# Connections.net
KiCad netlist of a schematic drawn in EAGLE
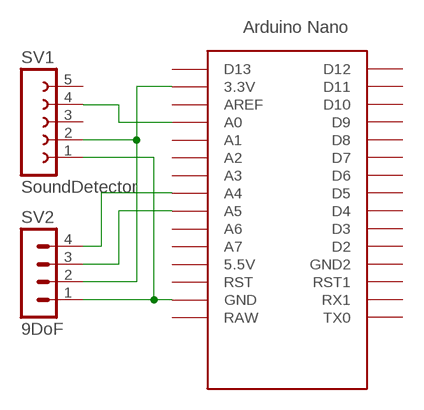
[diagram p0: schematic, sheet 1]

(export (version "E")
  (design (tool "Eeschema 10.0.6"))
  (components
    (comp (ref "SV1")
      (value "SoundDetector")
      (footprint "eagle-import:FE05-1")
      (libsource (lib "eagle-import") (part "FE05-1"))
    )
    (comp (ref "SV2")
      (value "9DoF")
      (footprint "eagle-import:MA04-1")
      (libsource (lib "eagle-import") (part "MA04-1"))
    )
    (comp (ref "U$1")
      (value "NANO")
      (footprint "eagle-import:NANO")
      (libsource (lib "eagle-import") (part "NANO"))
    )
  )
  (nets
    (net (code "1") (name "Net-(SV1-Pad1)") (class "Default")
      (node (ref "SV1") (pin "1") (pinfunction "1_1") (pintype "passive"))
      (node (ref "SV2") (pin "1") (pinfunction "1_1") (pintype "passive"))
      (node (ref "U$1") (pin "GND") (pinfunction "GND_GND") (pintype "bidirectional"))
    )
    (net (code "2") (name "Net-(SV1-Pad2)") (class "Default")
      (node (ref "SV1") (pin "2") (pinfunction "2_2") (pintype "passive"))
      (node (ref "SV2") (pin "2") (pinfunction "2_2") (pintype "passive"))
      (node (ref "U$1") (pin "3.3V") (pinfunction "3.3V_3.3V") (pintype "bidirectional"))
    )
    (net (code "3") (name "Net-(SV1-Pad4)") (class "Default")
      (node (ref "SV1") (pin "4") (pinfunction "4_4") (pintype "passive"))
      (node (ref "U$1") (pin "A0") (pinfunction "A0_A0") (pintype "bidirectional"))
    )
    (net (code "4") (name "Net-(SV2-Pad3)") (class "Default")
      (node (ref "SV2") (pin "3") (pinfunction "3_3") (pintype "passive"))
      (node (ref "U$1") (pin "A5") (pinfunction "A5_A5") (pintype "bidirectional"))
    )
    (net (code "5") (name "Net-(SV2-Pad4)") (class "Default")
      (node (ref "SV2") (pin "4") (pinfunction "4_4") (pintype "passive"))
      (node (ref "U$1") (pin "A4") (pinfunction "A4_A4") (pintype "bidirectional"))
    )
    (net (code "6") (name "unconnected-(SV1-Pad3)") (class "Default")
      (node (ref "SV1") (pin "3") (pinfunction "3_3") (pintype "passive"))
    )
    (net (code "7") (name "unconnected-(SV1-Pad5)") (class "Default")
      (node (ref "SV1") (pin "5") (pinfunction "5_5") (pintype "passive"))
    )
    (net (code "8") (name "unconnected-(U$1-5.5V-Pad5V)") (class "Default")
      (node (ref "U$1") (pin "5V") (pinfunction "5.5V_5V") (pintype "bidirectional"))
    )
    (net (code "9") (name "unconnected-(U$1-GND2-PadGND1)") (class "Default")
      (node (ref "U$1") (pin "GND1") (pinfunction "GND2_GND1") (pintype "bidirectional"))
    )
    (net (code "10") (name "unconnected-(U$1-PadA1)") (class "Default")
      (node (ref "U$1") (pin "A1") (pinfunction "A1_A1") (pintype "bidirectional"))
    )
    (net (code "11") (name "unconnected-(U$1-PadA2)") (class "Default")
      (node (ref "U$1") (pin "A2") (pinfunction "A2_A2") (pintype "bidirectional"))
    )
    (net (code "12") (name "unconnected-(U$1-PadA3)") (class "Default")
      (node (ref "U$1") (pin "A3") (pinfunction "A3_A3") (pintype "bidirectional"))
    )
    (net (code "13") (name "unconnected-(U$1-PadA6)") (class "Default")
      (node (ref "U$1") (pin "A6") (pinfunction "A6_A6") (pintype "bidirectional"))
    )
    (net (code "14") (name "unconnected-(U$1-PadA7)") (class "Default")
      (node (ref "U$1") (pin "A7") (pinfunction "A7_A7") (pintype "bidirectional"))
    )
    (net (code "15") (name "unconnected-(U$1-PadAREF)") (class "Default")
      (node (ref "U$1") (pin "AREF") (pinfunction "AREF_AREF") (pintype "bidirectional"))
    )
    (net (code "16") (name "unconnected-(U$1-PadD2)") (class "Default")
      (node (ref "U$1") (pin "D2") (pinfunction "D2_D2") (pintype "bidirectional"))
    )
    (net (code "17") (name "unconnected-(U$1-PadD3)") (class "Default")
      (node (ref "U$1") (pin "D3") (pinfunction "D3_D3") (pintype "bidirectional"))
    )
    (net (code "18") (name "unconnected-(U$1-PadD4)") (class "Default")
      (node (ref "U$1") (pin "D4") (pinfunction "D4_D4") (pintype "bidirectional"))
    )
    (net (code "19") (name "unconnected-(U$1-PadD5)") (class "Default")
      (node (ref "U$1") (pin "D5") (pinfunction "D5_D5") (pintype "bidirectional"))
    )
    (net (code "20") (name "unconnected-(U$1-PadD6)") (class "Default")
      (node (ref "U$1") (pin "D6") (pinfunction "D6_D6") (pintype "bidirectional"))
    )
    (net (code "21") (name "unconnected-(U$1-PadD7)") (class "Default")
      (node (ref "U$1") (pin "D7") (pinfunction "D7_D7") (pintype "bidirectional"))
    )
    (net (code "22") (name "unconnected-(U$1-PadD8)") (class "Default")
      (node (ref "U$1") (pin "D8") (pinfunction "D8_D8") (pintype "bidirectional"))
    )
    (net (code "23") (name "unconnected-(U$1-PadD9)") (class "Default")
      (node (ref "U$1") (pin "D9") (pinfunction "D9_D9") (pintype "bidirectional"))
    )
    (net (code "24") (name "unconnected-(U$1-PadD10)") (class "Default")
      (node (ref "U$1") (pin "D10") (pinfunction "D10_D10") (pintype "bidirectional"))
    )
    (net (code "25") (name "unconnected-(U$1-PadD11)") (class "Default")
      (node (ref "U$1") (pin "D11") (pinfunction "D11_D11") (pintype "bidirectional"))
    )
    (net (code "26") (name "unconnected-(U$1-PadD12)") (class "Default")
      (node (ref "U$1") (pin "D12") (pinfunction "D12_D12") (pintype "bidirectional"))
    )
    (net (code "27") (name "unconnected-(U$1-PadD13)") (class "Default")
      (node (ref "U$1") (pin "D13") (pinfunction "D13_D13") (pintype "bidirectional"))
    )
    (net (code "28") (name "unconnected-(U$1-PadICSP1)") (class "Default")
      (node (ref "U$1") (pin "ICSP1") (pinfunction "ICSP1_ICSP1") (pintype "bidirectional"))
    )
    (net (code "29") (name "unconnected-(U$1-PadICSP2)") (class "Default")
      (node (ref "U$1") (pin "ICSP2") (pinfunction "ICSP2_ICSP2") (pintype "bidirectional"))
    )
    (net (code "30") (name "unconnected-(U$1-PadICSP3)") (class "Default")
      (node (ref "U$1") (pin "ICSP3") (pinfunction "ICSP3_ICSP3") (pintype "bidirectional"))
    )
    (net (code "31") (name "unconnected-(U$1-PadICSP4)") (class "Default")
      (node (ref "U$1") (pin "ICSP4") (pinfunction "ICSP4_ICSP4") (pintype "bidirectional"))
    )
    (net (code "32") (name "unconnected-(U$1-PadICSP5)") (class "Default")
      (node (ref "U$1") (pin "ICSP5") (pinfunction "ICSP5_ICSP5") (pintype "bidirectional"))
    )
    (net (code "33") (name "unconnected-(U$1-PadICSP6)") (class "Default")
      (node (ref "U$1") (pin "ICSP6") (pinfunction "ICSP6_ICSP6") (pintype "bidirectional"))
    )
    (net (code "34") (name "unconnected-(U$1-PadRAW)") (class "Default")
      (node (ref "U$1") (pin "RAW") (pinfunction "RAW_RAW") (pintype "bidirectional"))
    )
    (net (code "35") (name "unconnected-(U$1-PadRST)") (class "Default")
      (node (ref "U$1") (pin "RST") (pinfunction "RST_RST") (pintype "bidirectional"))
    )
    (net (code "36") (name "unconnected-(U$1-PadRST1)") (class "Default")
      (node (ref "U$1") (pin "RST1") (pinfunction "RST1_RST1") (pintype "bidirectional"))
    )
    (net (code "37") (name "unconnected-(U$1-PadRX1)") (class "Default")
      (node (ref "U$1") (pin "RX1") (pinfunction "RX1_RX1") (pintype "bidirectional"))
    )
    (net (code "38") (name "unconnected-(U$1-PadTX0)") (class "Default")
      (node (ref "U$1") (pin "TX0") (pinfunction "TX0_TX0") (pintype "bidirectional"))
    )
  )
)
